# Connectors.net
KiCad netlist of a schematic drawn in Altium Designer
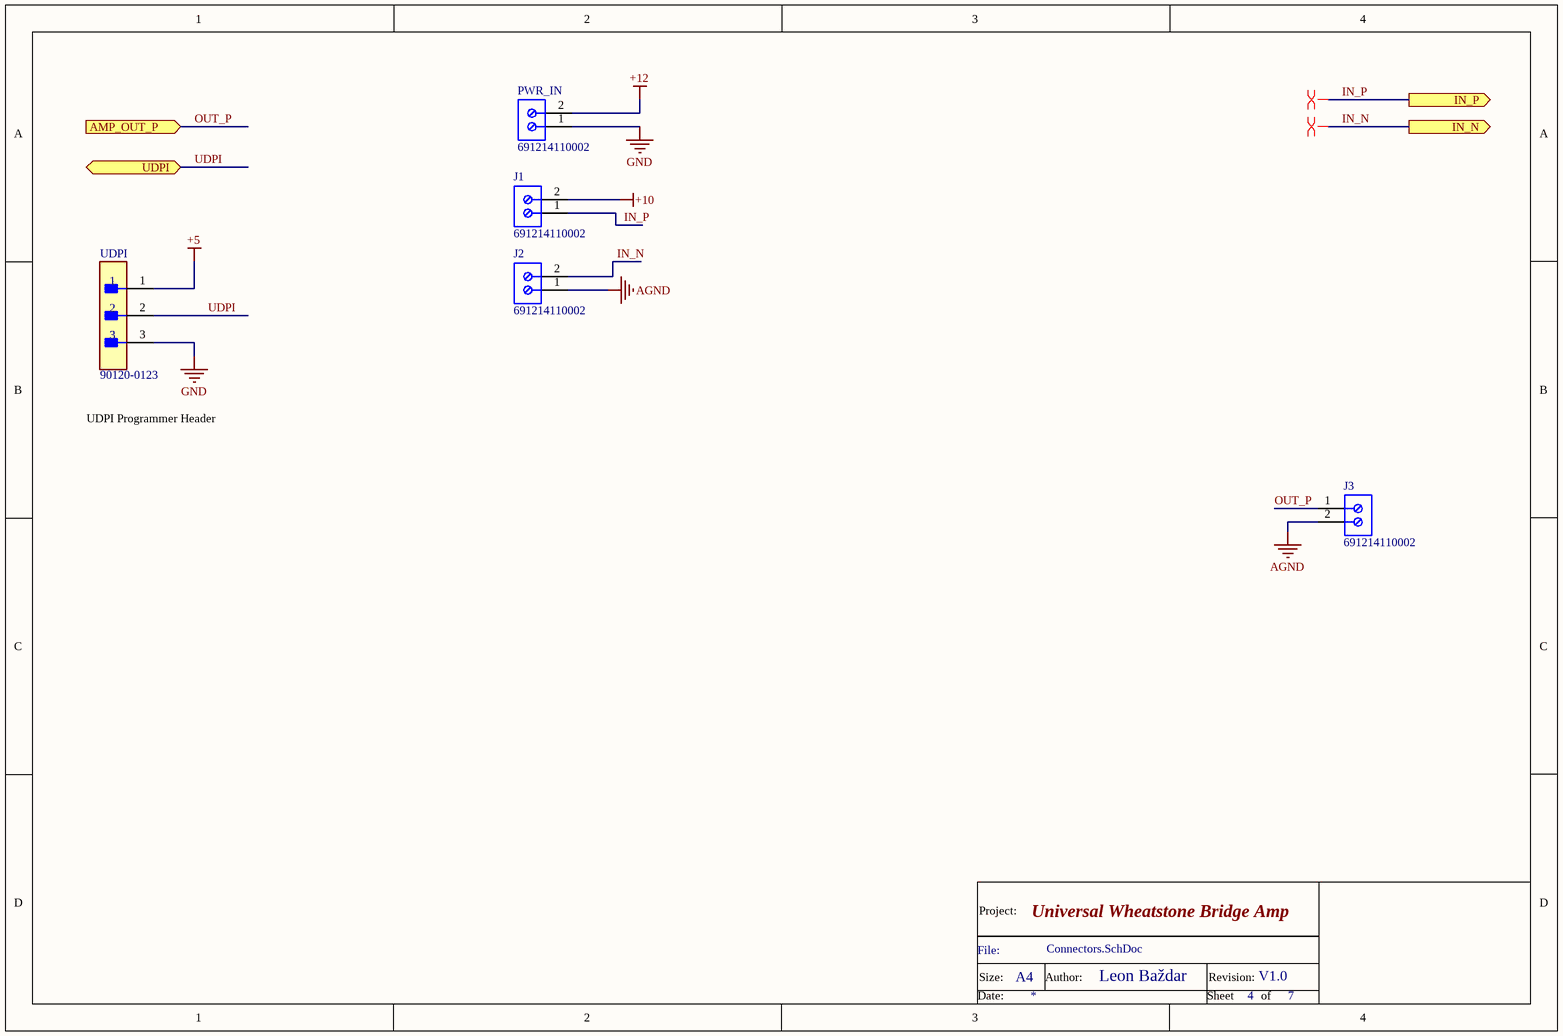
[diagram p0: Connectors.SchDoc]

(export (version "E")
  (design (tool "Eeschema 10.0.6"))
  (components
    (comp (ref "J1")
      (value "691214110002")
      (footprint "691214110002")
      (description "Serie 2141 - 3.50 mm Horizontal Entry Modular with Rising Cage Clamp WR-TBL, 2 pin")
      (fields (field (name "MANUFACTURER") "Wurth Elektronik") (field (name "PUBLISHER") "WurthElektronik"))
      (libsource (lib "Altium Content Vault") (part "WE-CN-1P-F-TB2"))
    )
    (comp (ref "J2")
      (value "691214110002")
      (footprint "691214110002")
      (description "Serie 2141 - 3.50 mm Horizontal Entry Modular with Rising Cage Clamp WR-TBL, 2 pin")
      (fields (field (name "MANUFACTURER") "Wurth Elektronik") (field (name "PUBLISHER") "WurthElektronik"))
      (libsource (lib "Altium Content Vault") (part "WE-CN-1P-F-TB2"))
    )
    (comp (ref "J3")
      (value "691214110002")
      (footprint "691214110002")
      (description "Serie 2141 - 3.50 mm Horizontal Entry Modular with Rising Cage Clamp WR-TBL, 2 pin")
      (fields (field (name "MANUFACTURER") "Wurth Elektronik") (field (name "PUBLISHER") "WurthElektronik"))
      (libsource (lib "Altium Content Vault") (part "WE-CN-1P-F-TB2"))
    )
    (comp (ref "PWR_IN")
      (value "691214110002")
      (footprint "691214110002")
      (description "Serie 2141 - 3.50 mm Horizontal Entry Modular with Rising Cage Clamp WR-TBL, 2 pin")
      (fields (field (name "MANUFACTURER") "Wurth Elektronik") (field (name "PUBLISHER") "WurthElektronik"))
      (libsource (lib "Altium Content Vault") (part "WE-CN-1P-F-TB2"))
    )
    (comp (ref "UDPI")
      (value "90120-0123")
      (footprint "FP-90120-0123-MFG")
      (description "CONN HEADER VERT 3POS 2.54MM")
      (libsource (lib "Altium Content Vault") (part "0d3f023dd272f625e17a2be33dea85f"))
    )
  )
  (nets
    (net (code "1") (name "+5") (class "Default")
      (node (ref "UDPI") (pin "1") (pinfunction "1_1") (pintype "passive"))
    )
    (net (code "2") (name "+10") (class "Default")
      (node (ref "J1") (pin "2") (pinfunction "2_2") (pintype "passive"))
    )
    (net (code "3") (name "+12") (class "Default")
      (node (ref "PWR_IN") (pin "2") (pinfunction "2_2") (pintype "passive"))
    )
    (net (code "4") (name "/IN_N") (class "Default")
      (node (ref "J2") (pin "2") (pinfunction "2_2") (pintype "passive"))
    )
    (net (code "5") (name "/IN_P") (class "Default")
      (node (ref "J1") (pin "1") (pinfunction "1_1") (pintype "passive"))
    )
    (net (code "6") (name "/OUT_P") (class "Default")
      (node (ref "J3") (pin "1") (pinfunction "1_1") (pintype "passive"))
    )
    (net (code "7") (name "/UDPI") (class "Default")
      (node (ref "UDPI") (pin "2") (pinfunction "2_2") (pintype "passive"))
    )
    (net (code "8") (name "AGND") (class "Default")
      (node (ref "J2") (pin "1") (pinfunction "1_1") (pintype "passive"))
      (node (ref "J3") (pin "2") (pinfunction "2_2") (pintype "passive"))
    )
    (net (code "9") (name "GND") (class "Default")
      (node (ref "PWR_IN") (pin "1") (pinfunction "1_1") (pintype "passive"))
      (node (ref "UDPI") (pin "3") (pinfunction "3_3") (pintype "passive"))
    )
  )
)
